# Sheet3.net
KiCad netlist of a schematic drawn in Altium Designer
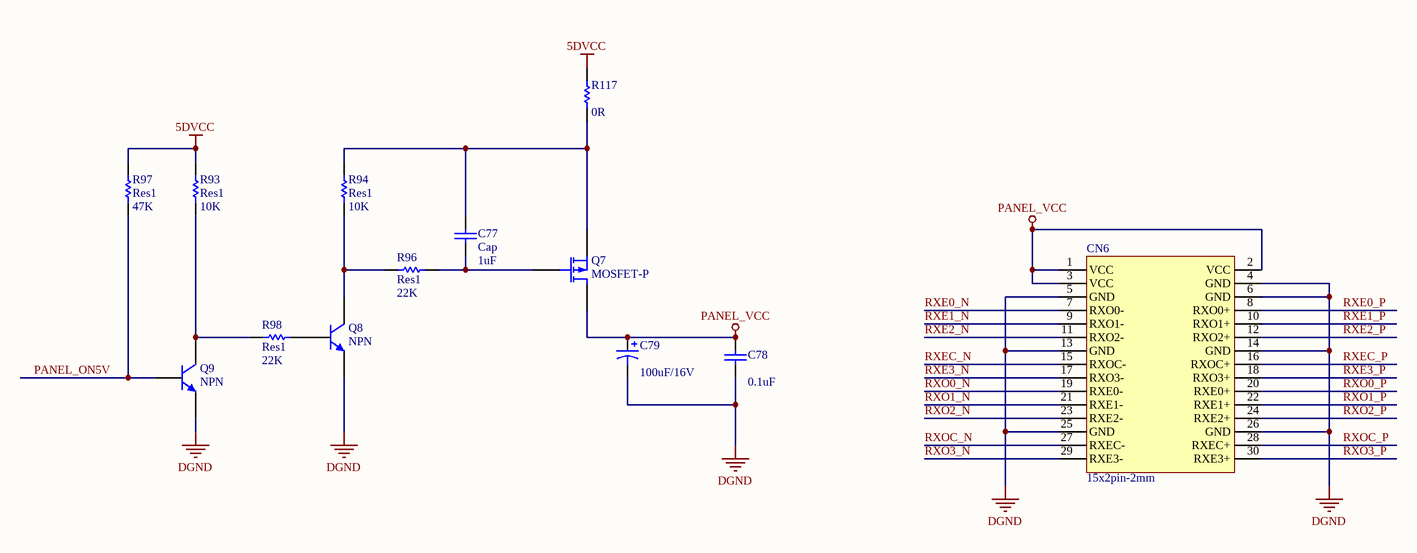
[diagram p0: Sheet3.SchDoc]

(export (version "E")
  (design (tool "Eeschema 10.0.6"))
  (components
    (comp (ref "C77")
      (value "Cap")
      (footprint "C-0402")
      (description "Capacitor")
      (fields (field (name "ALTIUM_VALUE") "1uF") (field (name "PUBLISHER") "Altium Limited"))
      (libsource (lib "Miscellaneous Devices") (part "Cap"))
    )
    (comp (ref "C78")
      (value "0.1uF")
      (footprint "C-0402")
      (description "Capacitor")
      (fields (field (name "Comment") "Cap") (field (name "PUBLISHER") "Altium Limited"))
      (libsource (lib "Miscellaneous Devices") (part "Cap"))
    )
    (comp (ref "C79")
      (value "100uF/16V")
      (footprint "CE-D3.6")
      (description "Polarized Capacitor (Radial)")
      (fields (field (name "Comment") "Cap Pol1") (field (name "PUBLISHER") "Altium Limited"))
      (libsource (lib "Miscellaneous Devices") (part "Cap Pol1"))
    )
    (comp (ref "CN6")
      (value "15x2pin-2mm")
      (footprint "JP-2*15")
      (libsource (lib "SCHLIB") (part "15x2pin-2mm"))
    )
    (comp (ref "Q7")
      (value "MOSFET-P")
      (footprint "Q-SOT23")
      (description "P-Channel MOSFET")
      (fields (field (name "PUBLISHER") "Altium Limited"))
      (libsource (lib "Miscellaneous Devices") (part "MOSFET-P"))
    )
    (comp (ref "Q8")
      (value "NPN")
      (footprint "Q-SOT23")
      (description "NPN Bipolar Transistor")
      (fields (field (name "PUBLISHER") "Altium Limited"))
      (libsource (lib "Miscellaneous Devices") (part "NPN"))
    )
    (comp (ref "Q9")
      (value "NPN")
      (footprint "Q-SOT23")
      (description "NPN Bipolar Transistor")
      (fields (field (name "PUBLISHER") "Altium Limited"))
      (libsource (lib "Miscellaneous Devices") (part "NPN"))
    )
    (comp (ref "R93")
      (value "Res1")
      (footprint "R-0603")
      (description "Resistor")
      (fields (field (name "ALTIUM_VALUE") "10K") (field (name "PUBLISHER") "Altium Limited"))
      (libsource (lib "Miscellaneous Devices") (part "Res1"))
    )
    (comp (ref "R94")
      (value "Res1")
      (footprint "R-0603")
      (description "Resistor")
      (fields (field (name "ALTIUM_VALUE") "10K") (field (name "PUBLISHER") "Altium Limited"))
      (libsource (lib "Miscellaneous Devices") (part "Res1"))
    )
    (comp (ref "R96")
      (value "Res1")
      (footprint "R-0603")
      (description "Resistor")
      (fields (field (name "ALTIUM_VALUE") "22K") (field (name "PUBLISHER") "Altium Limited"))
      (libsource (lib "Miscellaneous Devices") (part "Res1"))
    )
    (comp (ref "R97")
      (value "Res1")
      (footprint "R-0603")
      (description "Resistor")
      (fields (field (name "ALTIUM_VALUE") "47K") (field (name "PUBLISHER") "Altium Limited"))
      (libsource (lib "Miscellaneous Devices") (part "Res1"))
    )
    (comp (ref "R98")
      (value "Res1")
      (footprint "R-0603")
      (description "Resistor")
      (fields (field (name "ALTIUM_VALUE") "22K") (field (name "PUBLISHER") "Altium Limited"))
      (libsource (lib "Miscellaneous Devices") (part "Res1"))
    )
    (comp (ref "R117")
      (value "0R")
      (footprint "R-0805")
      (description "Resistor")
      (fields (field (name "Comment") "Res1") (field (name "PUBLISHER") "Altium Limited"))
      (libsource (lib "Miscellaneous Devices") (part "Res1"))
    )
  )
  (nets
    (net (code "1") (name "/PANEL_ON5V") (class "Default")
      (node (ref "Q9") (pin "2") (pinfunction "B_2") (pintype "passive"))
      (node (ref "R97") (pin "1") (pinfunction "1_1") (pintype "passive"))
    )
    (net (code "2") (name "/RXE0_N") (class "Default")
      (node (ref "CN6") (pin "7") (pinfunction "RXO0-_7") (pintype "passive"))
    )
    (net (code "3") (name "/RXE0_P") (class "Default")
      (node (ref "CN6") (pin "8") (pinfunction "RXO0+_8") (pintype "passive"))
    )
    (net (code "4") (name "/RXE1_N") (class "Default")
      (node (ref "CN6") (pin "9") (pinfunction "RXO1-_9") (pintype "passive"))
    )
    (net (code "5") (name "/RXE1_P") (class "Default")
      (node (ref "CN6") (pin "10") (pinfunction "RXO1+_10") (pintype "passive"))
    )
    (net (code "6") (name "/RXE2_N") (class "Default")
      (node (ref "CN6") (pin "11") (pinfunction "RXO2-_11") (pintype "passive"))
    )
    (net (code "7") (name "/RXE2_P") (class "Default")
      (node (ref "CN6") (pin "12") (pinfunction "RXO2+_12") (pintype "passive"))
    )
    (net (code "8") (name "/RXE3_N") (class "Default")
      (node (ref "CN6") (pin "17") (pinfunction "RXO3-_17") (pintype "passive"))
    )
    (net (code "9") (name "/RXE3_P") (class "Default")
      (node (ref "CN6") (pin "18") (pinfunction "RXO3+_18") (pintype "passive"))
    )
    (net (code "10") (name "/RXEC_N") (class "Default")
      (node (ref "CN6") (pin "15") (pinfunction "RXOC-_15") (pintype "passive"))
    )
    (net (code "11") (name "/RXEC_P") (class "Default")
      (node (ref "CN6") (pin "16") (pinfunction "RXOC+_16") (pintype "passive"))
    )
    (net (code "12") (name "/RXO0_N") (class "Default")
      (node (ref "CN6") (pin "19") (pinfunction "RXE0-_19") (pintype "passive"))
    )
    (net (code "13") (name "/RXO0_P") (class "Default")
      (node (ref "CN6") (pin "20") (pinfunction "RXE0+_20") (pintype "passive"))
    )
    (net (code "14") (name "/RXO1_N") (class "Default")
      (node (ref "CN6") (pin "21") (pinfunction "RXE1-_21") (pintype "passive"))
    )
    (net (code "15") (name "/RXO1_P") (class "Default")
      (node (ref "CN6") (pin "22") (pinfunction "RXE1+_22") (pintype "passive"))
    )
    (net (code "16") (name "/RXO2_N") (class "Default")
      (node (ref "CN6") (pin "23") (pinfunction "RXE2-_23") (pintype "passive"))
    )
    (net (code "17") (name "/RXO2_P") (class "Default")
      (node (ref "CN6") (pin "24") (pinfunction "RXE2+_24") (pintype "passive"))
    )
    (net (code "18") (name "/RXO3_N") (class "Default")
      (node (ref "CN6") (pin "29") (pinfunction "RXE3-_29") (pintype "passive"))
    )
    (net (code "19") (name "/RXO3_P") (class "Default")
      (node (ref "CN6") (pin "30") (pinfunction "RXE3+_30") (pintype "passive"))
    )
    (net (code "20") (name "/RXOC_N") (class "Default")
      (node (ref "CN6") (pin "27") (pinfunction "RXEC-_27") (pintype "passive"))
    )
    (net (code "21") (name "/RXOC_P") (class "Default")
      (node (ref "CN6") (pin "28") (pinfunction "RXEC+_28") (pintype "passive"))
    )
    (net (code "22") (name "5DVCC") (class "Default")
      (node (ref "R117") (pin "1") (pinfunction "1_1") (pintype "passive"))
      (node (ref "R93") (pin "2") (pinfunction "2_2") (pintype "passive"))
      (node (ref "R97") (pin "2") (pinfunction "2_2") (pintype "passive"))
    )
    (net (code "23") (name "DGND") (class "Default")
      (node (ref "C78") (pin "2") (pinfunction "2_2") (pintype "passive"))
      (node (ref "C79") (pin "2") (pinfunction "2_2") (pintype "passive"))
      (node (ref "CN6") (pin "13") (pinfunction "GND_13") (pintype "passive"))
      (node (ref "CN6") (pin "14") (pinfunction "GND_14") (pintype "passive"))
      (node (ref "CN6") (pin "25") (pinfunction "GND_25") (pintype "passive"))
      (node (ref "CN6") (pin "26") (pinfunction "GND_26") (pintype "passive"))
      (node (ref "CN6") (pin "4") (pinfunction "GND_4") (pintype "passive"))
      (node (ref "CN6") (pin "5") (pinfunction "GND_5") (pintype "passive"))
      (node (ref "CN6") (pin "6") (pinfunction "GND_6") (pintype "passive"))
      (node (ref "Q8") (pin "3") (pinfunction "E_3") (pintype "passive"))
      (node (ref "Q9") (pin "3") (pinfunction "E_3") (pintype "passive"))
    )
    (net (code "24") (name "Net-(Q7-G)") (class "Default")
      (node (ref "C77") (pin "2") (pinfunction "2_2") (pintype "passive"))
      (node (ref "Q7") (pin "2") (pinfunction "G_2") (pintype "passive"))
      (node (ref "R96") (pin "1") (pinfunction "1_1") (pintype "passive"))
    )
    (net (code "25") (name "Net-(Q7-S)") (class "Default")
      (node (ref "C77") (pin "1") (pinfunction "1_1") (pintype "passive"))
      (node (ref "Q7") (pin "3") (pinfunction "S_3") (pintype "passive"))
      (node (ref "R117") (pin "2") (pinfunction "2_2") (pintype "passive"))
      (node (ref "R94") (pin "1") (pinfunction "1_1") (pintype "passive"))
    )
    (net (code "26") (name "Net-(Q8-B)") (class "Default")
      (node (ref "Q8") (pin "2") (pinfunction "B_2") (pintype "passive"))
      (node (ref "R98") (pin "1") (pinfunction "1_1") (pintype "passive"))
    )
    (net (code "27") (name "Net-(Q8-C)") (class "Default")
      (node (ref "Q8") (pin "1") (pinfunction "C_1") (pintype "passive"))
      (node (ref "R94") (pin "2") (pinfunction "2_2") (pintype "passive"))
      (node (ref "R96") (pin "2") (pinfunction "2_2") (pintype "passive"))
    )
    (net (code "28") (name "Net-(Q9-C)") (class "Default")
      (node (ref "Q9") (pin "1") (pinfunction "C_1") (pintype "passive"))
      (node (ref "R93") (pin "1") (pinfunction "1_1") (pintype "passive"))
      (node (ref "R98") (pin "2") (pinfunction "2_2") (pintype "passive"))
    )
    (net (code "29") (name "PANEL_VCC") (class "Default")
      (node (ref "C78") (pin "1") (pinfunction "1_1") (pintype "passive"))
      (node (ref "C79") (pin "1") (pinfunction "1_1") (pintype "passive"))
      (node (ref "CN6") (pin "1") (pinfunction "VCC_1") (pintype "passive"))
      (node (ref "CN6") (pin "2") (pinfunction "VCC_2") (pintype "passive"))
      (node (ref "CN6") (pin "3") (pinfunction "VCC_3") (pintype "passive"))
      (node (ref "Q7") (pin "1") (pinfunction "D_1") (pintype "passive"))
    )
  )
)
